# remote-display.net
KiCad netlist of a schematic drawn in EAGLE
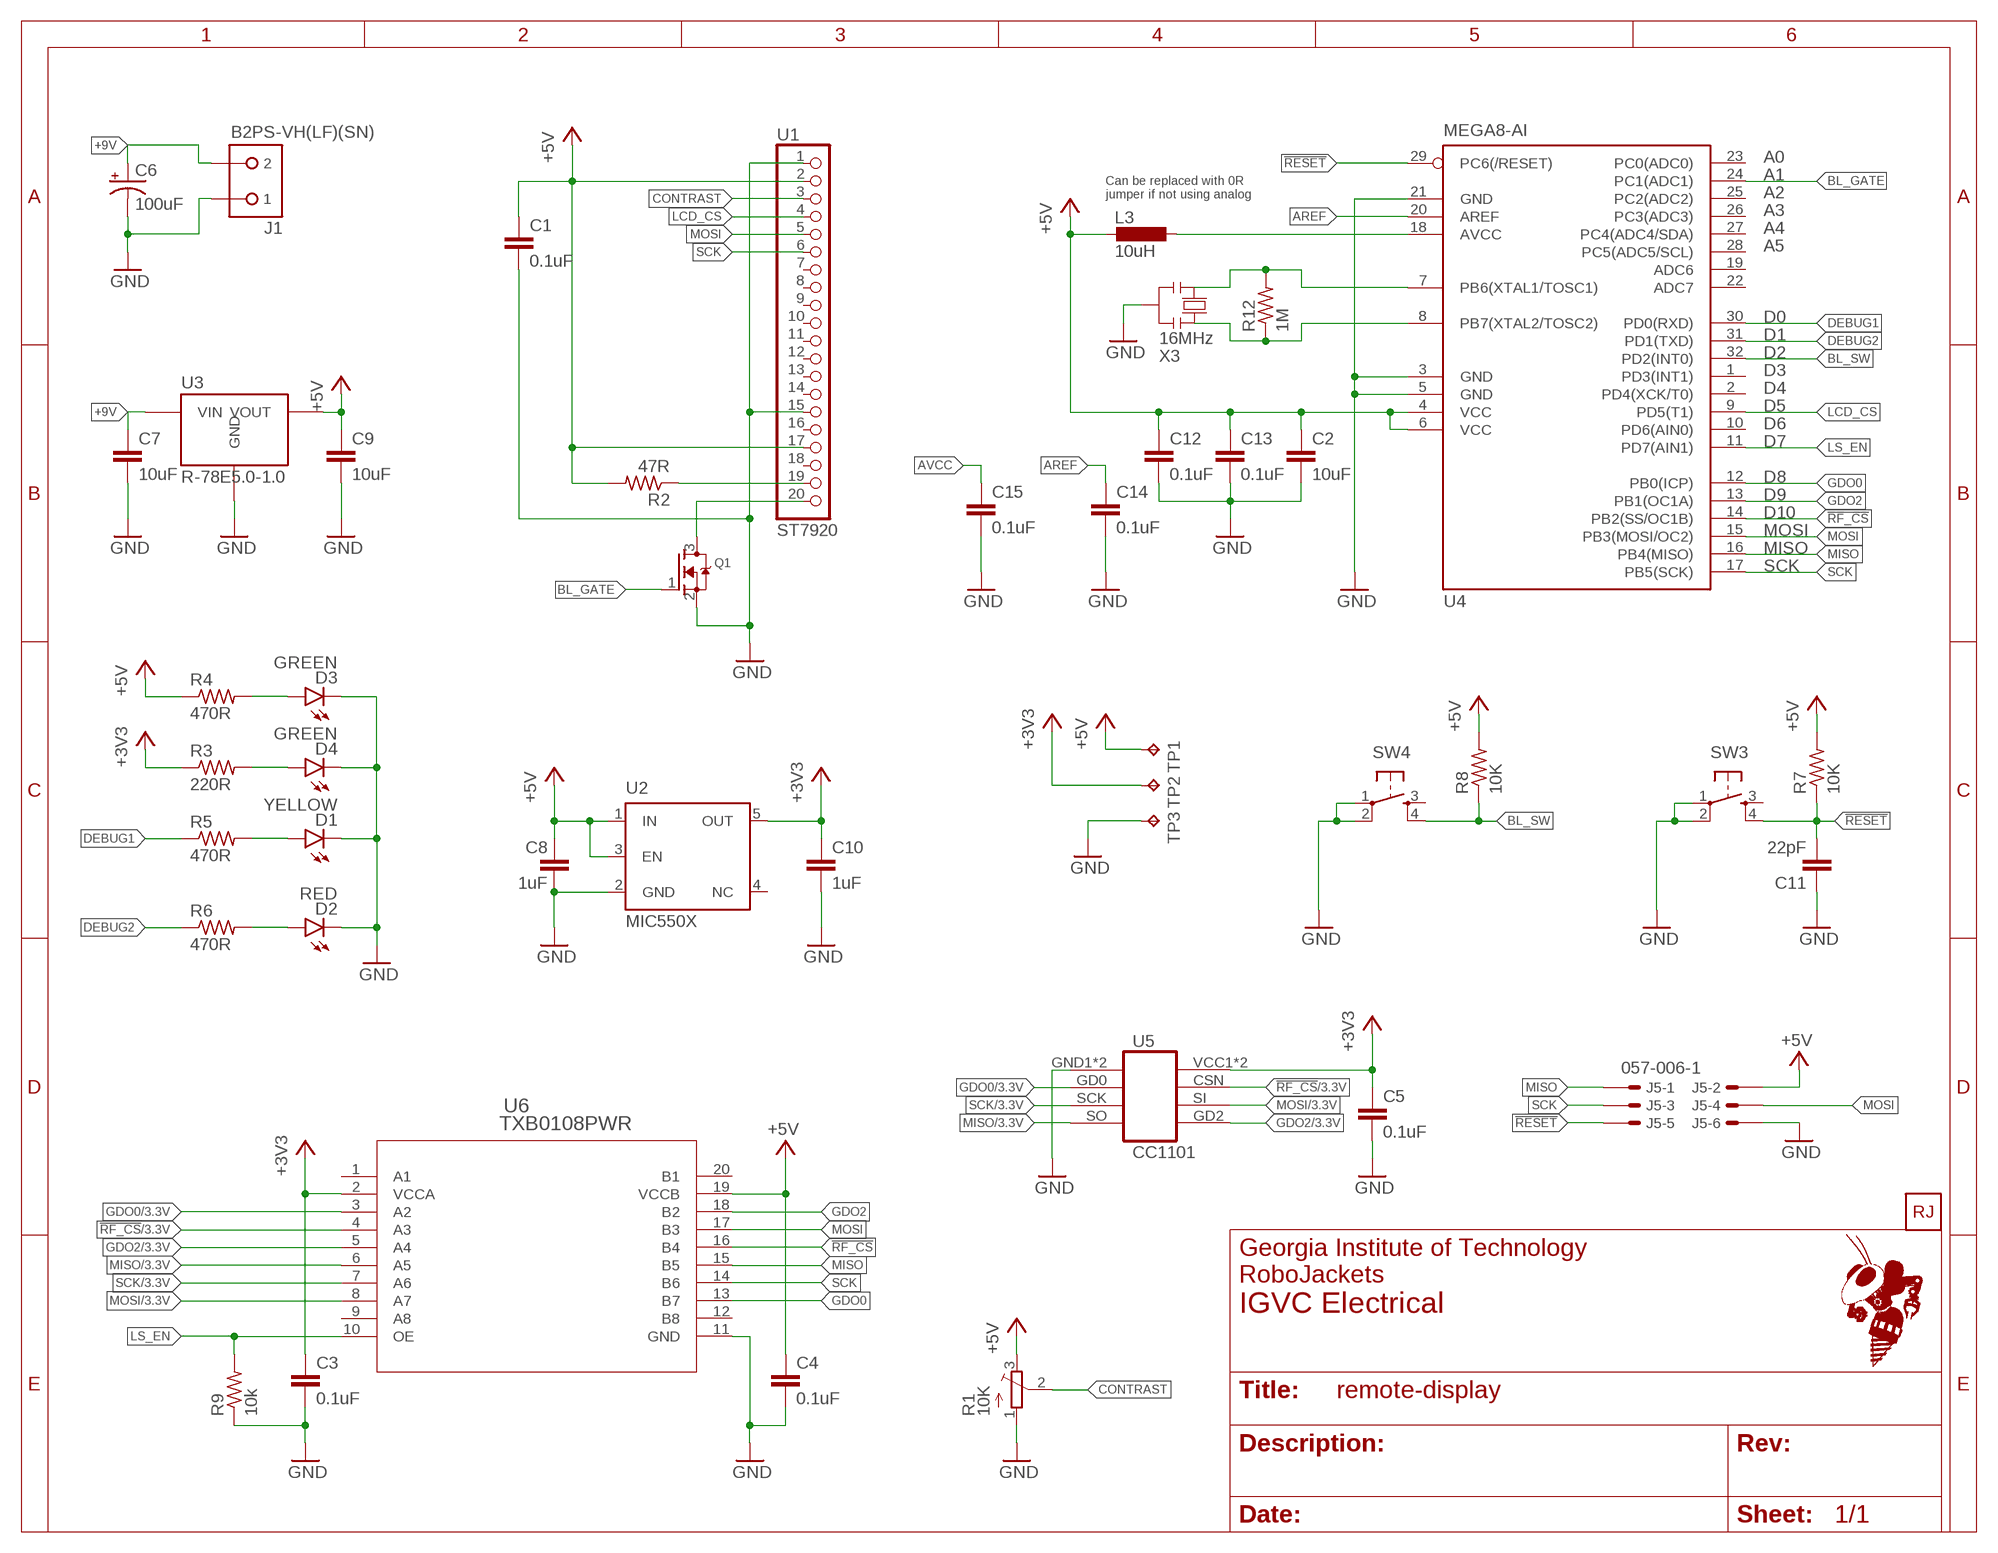
[diagram p0: schematic, sheet 1]

(export (version "E")
  (design (tool "Eeschema 10.0.6"))
  (components
    (comp (ref "C1")
      (value "0.1uF")
      (footprint "eagle-import:C0603")
      (libsource (lib "eagle-import") (part "resistor_348_C-EUC0603"))
    )
    (comp (ref "C2")
      (value "10uF")
      (footprint "eagle-import:C0805")
      (libsource (lib "eagle-import") (part "resistor_348_C-EUC0805"))
    )
    (comp (ref "C3")
      (value "0.1uF")
      (footprint "eagle-import:C0603")
      (libsource (lib "eagle-import") (part "C-EUC0603"))
    )
    (comp (ref "C4")
      (value "0.1uF")
      (footprint "eagle-import:C0603")
      (libsource (lib "eagle-import") (part "C-EUC0603"))
    )
    (comp (ref "C5")
      (value "0.1uF")
      (footprint "eagle-import:C0603")
      (libsource (lib "eagle-import") (part "resistor_348_C-EUC0603"))
    )
    (comp (ref "C6")
      (value "100uF")
      (footprint "eagle-import:E5-10,5")
      (libsource (lib "eagle-import") (part "CPOL-USE5-10.5"))
    )
    (comp (ref "C7")
      (value "10uF")
      (footprint "eagle-import:C0603")
      (libsource (lib "eagle-import") (part "C-EUC0603"))
    )
    (comp (ref "C8")
      (value "1uF")
      (footprint "eagle-import:C0603")
      (libsource (lib "eagle-import") (part "C-EUC0603"))
    )
    (comp (ref "C9")
      (value "10uF")
      (footprint "eagle-import:C0603")
      (libsource (lib "eagle-import") (part "C-EUC0603"))
    )
    (comp (ref "C10")
      (value "1uF")
      (footprint "eagle-import:C0603")
      (libsource (lib "eagle-import") (part "C-EUC0603"))
    )
    (comp (ref "C11")
      (value "22pF")
      (footprint "eagle-import:C0603")
      (libsource (lib "eagle-import") (part "resistor_348_C-EUC0603"))
    )
    (comp (ref "C12")
      (value "0.1uF")
      (footprint "eagle-import:C0603")
      (libsource (lib "eagle-import") (part "resistor_348_C-EUC0603"))
    )
    (comp (ref "C13")
      (value "0.1uF")
      (footprint "eagle-import:C0603")
      (libsource (lib "eagle-import") (part "resistor_348_C-EUC0603"))
    )
    (comp (ref "C14")
      (value "0.1uF")
      (footprint "eagle-import:C0603")
      (libsource (lib "eagle-import") (part "resistor_348_C-EUC0603"))
    )
    (comp (ref "C15")
      (value "0.1uF")
      (footprint "eagle-import:C0603")
      (libsource (lib "eagle-import") (part "resistor_348_C-EUC0603"))
    )
    (comp (ref "D1")
      (value "YELLOW")
      (footprint "eagle-import:LED3MM")
      (libsource (lib "eagle-import") (part "LED3MM"))
    )
    (comp (ref "D2")
      (value "RED")
      (footprint "eagle-import:LED3MM")
      (libsource (lib "eagle-import") (part "LED3MM"))
    )
    (comp (ref "D3")
      (value "GREEN")
      (footprint "eagle-import:LED3MM")
      (libsource (lib "eagle-import") (part "LED3MM"))
    )
    (comp (ref "D4")
      (value "GREEN")
      (footprint "eagle-import:LED3MM")
      (libsource (lib "eagle-import") (part "LED3MM"))
    )
    (comp (ref "J1")
      (value "B2PS-VH(LF)(SN)")
      (footprint "eagle-import:B2PS-CENTERED")
      (libsource (lib "eagle-import") (part "B2P?-VH(LF)(SN)S"))
    )
    (comp (ref "J5")
      (value "057-006-1")
      (footprint "eagle-import:057-006-1")
      (fields (field (name "DIGIKEY") "3M15451-ND"))
      (libsource (lib "eagle-import") (part "057-006-1"))
    )
    (comp (ref "L3")
      (value "10uH")
      (footprint "eagle-import:0805")
      (libsource (lib "eagle-import") (part "L-0805"))
    )
    (comp (ref "Q1")
      (value "MOSFET-NREFLOW")
      (footprint "eagle-import:SOT23")
      (libsource (lib "eagle-import") (part "MOSFET-NREFLOW"))
    )
    (comp (ref "R1")
      (value "10K")
      (footprint "eagle-import:TRIM-3386")
      (libsource (lib "eagle-import") (part "TRIMPOT3386"))
    )
    (comp (ref "R2")
      (value "47R")
      (footprint "eagle-import:R0805")
      (libsource (lib "eagle-import") (part "resistor_348_R-US_R0805"))
    )
    (comp (ref "R3")
      (value "220R")
      (footprint "eagle-import:R0603")
      (libsource (lib "eagle-import") (part "resistor_348_R-US_R0603"))
    )
    (comp (ref "R4")
      (value "470R")
      (footprint "eagle-import:R0603")
      (libsource (lib "eagle-import") (part "resistor_348_R-US_R0603"))
    )
    (comp (ref "R5")
      (value "470R")
      (footprint "eagle-import:R0603")
      (libsource (lib "eagle-import") (part "resistor_348_R-US_R0603"))
    )
    (comp (ref "R6")
      (value "470R")
      (footprint "eagle-import:R0603")
      (libsource (lib "eagle-import") (part "resistor_348_R-US_R0603"))
    )
    (comp (ref "R7")
      (value "10K")
      (footprint "eagle-import:R0603")
      (libsource (lib "eagle-import") (part "resistor_348_R-US_R0603"))
    )
    (comp (ref "R8")
      (value "10K")
      (footprint "eagle-import:R0603")
      (libsource (lib "eagle-import") (part "resistor_348_R-US_R0603"))
    )
    (comp (ref "R9")
      (value "10k")
      (footprint "eagle-import:R0603")
      (libsource (lib "eagle-import") (part "R-US_R0603"))
    )
    (comp (ref "R12")
      (value "1M")
      (footprint "eagle-import:R0603")
      (libsource (lib "eagle-import") (part "resistor_348_R-US_R0603"))
    )
    (comp (ref "SW3")
      (value "TL1105_A-H")
      (footprint "eagle-import:TL1105_A-H")
      (libsource (lib "eagle-import") (part "TL1105_A-H"))
    )
    (comp (ref "SW4")
      (value "TL1105_A-H")
      (footprint "eagle-import:TL1105_A-H")
      (libsource (lib "eagle-import") (part "TL1105_A-H"))
    )
    (comp (ref "TP1")
      (value "TPPAD1-17")
      (footprint "eagle-import:P1-17")
      (libsource (lib "eagle-import") (part "TPPAD1-17"))
    )
    (comp (ref "TP2")
      (value "TPPAD1-17")
      (footprint "eagle-import:P1-17")
      (libsource (lib "eagle-import") (part "TPPAD1-17"))
    )
    (comp (ref "TP3")
      (value "TPPAD1-17")
      (footprint "eagle-import:P1-17")
      (libsource (lib "eagle-import") (part "TPPAD1-17"))
    )
    (comp (ref "U$2")
      (value "ROBOBUZZ1.0X")
      (footprint "eagle-import:ROBOBUZZ_1.0X")
      (libsource (lib "eagle-import") (part "ROBOBUZZ1.0X"))
    )
    (comp (ref "U1")
      (value "ST7920")
      (footprint "eagle-import:ST7920-LCD")
      (libsource (lib "eagle-import") (part "ST7920"))
    )
    (comp (ref "U2")
      (value "MIC550X")
      (footprint "eagle-import:SOT23-DBV")
      (libsource (lib "eagle-import") (part "MIC550X"))
    )
    (comp (ref "U3")
      (value "R-78E5.0-1.0")
      (footprint "eagle-import:R-78E")
      (libsource (lib "eagle-import") (part "R-78E5.0-1.0"))
    )
    (comp (ref "U4")
      (value "MEGA8-AI")
      (footprint "eagle-import:TQFP32-08")
      (fields (field (name "MPN") "ATMEGA8-16AU"))
      (libsource (lib "eagle-import") (part "MEGA8-AI"))
    )
    (comp (ref "U5")
      (value "CC1101")
      (footprint "eagle-import:TI-CC1101")
      (libsource (lib "eagle-import") (part "NRF24L01+PA+LNATI-CC1101"))
    )
    (comp (ref "U6")
      (value "TXB0108PWR")
      (footprint "eagle-import:PW20")
      (libsource (lib "eagle-import") (part "TXB0108PWR"))
    )
    (comp (ref "X3")
      (value "16MHz")
      (footprint "eagle-import:RESONATOR")
      (fields (field (name "PART_NUMBER") "CSTCE16M0V53-R0"))
      (libsource (lib "eagle-import") (part "OSC_CSTCE16M0V53-R0"))
    )
  )
  (nets
    (net (code "1") (name "+3V3") (class "Default")
      (node (ref "C10") (pin "1") (pinfunction "1_1") (pintype "passive"))
      (node (ref "C3") (pin "1") (pinfunction "1_1") (pintype "passive"))
      (node (ref "C5") (pin "1") (pinfunction "1_1") (pintype "passive"))
      (node (ref "R3") (pin "1") (pinfunction "1_1") (pintype "passive"))
      (node (ref "TP2") (pin "TP") (pinfunction "TP_TP") (pintype "input"))
      (node (ref "U2") (pin "5") (pinfunction "OUT_5") (pintype "passive"))
      (node (ref "U5") (pin "VCC1") (pinfunction "VCC_VCC1") (pintype "power_in"))
      (node (ref "U5") (pin "VCC2") (pinfunction "VCC_VCC2") (pintype "power_in"))
      (node (ref "U6") (pin "2") (pinfunction "VCCA_2") (pintype "power_in"))
    )
    (net (code "2") (name "+5V") (class "Default")
      (node (ref "C1") (pin "1") (pinfunction "1_1") (pintype "passive"))
      (node (ref "C12") (pin "1") (pinfunction "1_1") (pintype "passive"))
      (node (ref "C13") (pin "1") (pinfunction "1_1") (pintype "passive"))
      (node (ref "C2") (pin "1") (pinfunction "1_1") (pintype "passive"))
      (node (ref "C4") (pin "1") (pinfunction "1_1") (pintype "passive"))
      (node (ref "C8") (pin "1") (pinfunction "1_1") (pintype "passive"))
      (node (ref "C9") (pin "1") (pinfunction "1_1") (pintype "passive"))
      (node (ref "J5") (pin "2") (pinfunction "S_2") (pintype "passive"))
      (node (ref "L3") (pin "2") (pinfunction "2_2") (pintype "passive"))
      (node (ref "R1") (pin "3") (pinfunction "E_3") (pintype "passive"))
      (node (ref "R2") (pin "2") (pinfunction "2_2") (pintype "passive"))
      (node (ref "R4") (pin "1") (pinfunction "1_1") (pintype "passive"))
      (node (ref "R7") (pin "2") (pinfunction "2_2") (pintype "passive"))
      (node (ref "R8") (pin "2") (pinfunction "2_2") (pintype "passive"))
      (node (ref "TP1") (pin "TP") (pinfunction "TP_TP") (pintype "input"))
      (node (ref "U1") (pin "17") (pinfunction "17_17") (pintype "passive"))
      (node (ref "U1") (pin "2") (pinfunction "2_2") (pintype "passive"))
      (node (ref "U2") (pin "1") (pinfunction "IN_1") (pintype "input"))
      (node (ref "U2") (pin "3") (pinfunction "EN_3") (pintype "input"))
      (node (ref "U3") (pin "3") (pinfunction "VOUT_3") (pintype "bidirectional"))
      (node (ref "U4") (pin "4") (pinfunction "VCC_4") (pintype "power_in"))
      (node (ref "U4") (pin "6") (pinfunction "VCC_6") (pintype "power_in"))
      (node (ref "U6") (pin "19") (pinfunction "VCCB_19") (pintype "power_in"))
    )
    (net (code "3") (name "+9V") (class "Default")
      (node (ref "C6") (pin "+") (pinfunction "+_+") (pintype "passive"))
      (node (ref "C7") (pin "1") (pinfunction "1_1") (pintype "passive"))
      (node (ref "J1") (pin "2") (pinfunction "2_2") (pintype "bidirectional"))
      (node (ref "U3") (pin "1") (pinfunction "VIN_1") (pintype "bidirectional"))
    )
    (net (code "4") (name "/~{RESET}") (class "Default")
      (node (ref "C11") (pin "2") (pinfunction "2_2") (pintype "passive"))
      (node (ref "J5") (pin "5") (pinfunction "S_5") (pintype "passive"))
      (node (ref "R7") (pin "1") (pinfunction "1_1") (pintype "passive"))
      (node (ref "SW3") (pin "4") (pinfunction "4_4") (pintype "passive"))
      (node (ref "U4") (pin "29") (pinfunction "PC6(/RESET)_29") (pintype "bidirectional"))
    )
    (net (code "5") (name "/~{RF_CS}") (class "Default")
      (node (ref "U4") (pin "14") (pinfunction "PB2(SS/OC1B)_14") (pintype "bidirectional"))
      (node (ref "U6") (pin "16") (pinfunction "B4_16") (pintype "bidirectional"))
    )
    (net (code "6") (name "/~{RF_CS}{slash}3.3V") (class "Default")
      (node (ref "U5") (pin "CSN") (pinfunction "CSN_CSN") (pintype "passive"))
      (node (ref "U6") (pin "4") (pinfunction "A3_4") (pintype "bidirectional"))
    )
    (net (code "7") (name "AREF") (class "Default")
      (node (ref "C14") (pin "1") (pinfunction "1_1") (pintype "passive"))
      (node (ref "U4") (pin "20") (pinfunction "AREF_20") (pintype "passive"))
    )
    (net (code "8") (name "AVCC") (class "Default")
      (node (ref "C15") (pin "1") (pinfunction "1_1") (pintype "passive"))
      (node (ref "L3") (pin "1") (pinfunction "1_1") (pintype "passive"))
      (node (ref "U4") (pin "18") (pinfunction "AVCC_18") (pintype "power_in"))
    )
    (net (code "9") (name "BL_GATE") (class "Default")
      (node (ref "Q1") (pin "1") (pinfunction "G_1") (pintype "bidirectional"))
      (node (ref "U4") (pin "24") (pinfunction "PC1(ADC1)_24") (pintype "bidirectional"))
    )
    (net (code "10") (name "BL_SW") (class "Default")
      (node (ref "R8") (pin "1") (pinfunction "1_1") (pintype "passive"))
      (node (ref "SW4") (pin "4") (pinfunction "4_4") (pintype "passive"))
      (node (ref "U4") (pin "32") (pinfunction "PD2(INT0)_32") (pintype "bidirectional"))
    )
    (net (code "11") (name "CONTRAST") (class "Default")
      (node (ref "R1") (pin "2") (pinfunction "S_2") (pintype "passive"))
      (node (ref "U1") (pin "3") (pinfunction "3_3") (pintype "passive"))
    )
    (net (code "12") (name "DEBUG1") (class "Default")
      (node (ref "R5") (pin "1") (pinfunction "1_1") (pintype "passive"))
      (node (ref "U4") (pin "30") (pinfunction "PD0(RXD)_30") (pintype "bidirectional"))
    )
    (net (code "13") (name "DEBUG2") (class "Default")
      (node (ref "R6") (pin "1") (pinfunction "1_1") (pintype "passive"))
      (node (ref "U4") (pin "31") (pinfunction "PD1(TXD)_31") (pintype "bidirectional"))
    )
    (net (code "14") (name "GDO0") (class "Default")
      (node (ref "U4") (pin "12") (pinfunction "PB0(ICP)_12") (pintype "bidirectional"))
      (node (ref "U6") (pin "13") (pinfunction "B7_13") (pintype "bidirectional"))
    )
    (net (code "15") (name "GDO0{slash}3.3V") (class "Default")
      (node (ref "U5") (pin "GD0") (pinfunction "CE_GD0") (pintype "passive"))
      (node (ref "U6") (pin "3") (pinfunction "A2_3") (pintype "bidirectional"))
    )
    (net (code "16") (name "GDO2") (class "Default")
      (node (ref "U4") (pin "13") (pinfunction "PB1(OC1A)_13") (pintype "bidirectional"))
      (node (ref "U6") (pin "18") (pinfunction "B2_18") (pintype "bidirectional"))
    )
    (net (code "17") (name "GDO2{slash}3.3V") (class "Default")
      (node (ref "U5") (pin "GD2") (pinfunction "IRQ_GD2") (pintype "passive"))
      (node (ref "U6") (pin "5") (pinfunction "A4_5") (pintype "bidirectional"))
    )
    (net (code "18") (name "GND") (class "Default")
      (node (ref "C1") (pin "2") (pinfunction "2_2") (pintype "passive"))
      (node (ref "C10") (pin "2") (pinfunction "2_2") (pintype "passive"))
      (node (ref "C11") (pin "1") (pinfunction "1_1") (pintype "passive"))
      (node (ref "C12") (pin "2") (pinfunction "2_2") (pintype "passive"))
      (node (ref "C13") (pin "2") (pinfunction "2_2") (pintype "passive"))
      (node (ref "C14") (pin "2") (pinfunction "2_2") (pintype "passive"))
      (node (ref "C15") (pin "2") (pinfunction "2_2") (pintype "passive"))
      (node (ref "C2") (pin "2") (pinfunction "2_2") (pintype "passive"))
      (node (ref "C3") (pin "2") (pinfunction "2_2") (pintype "passive"))
      (node (ref "C4") (pin "2") (pinfunction "2_2") (pintype "passive"))
      (node (ref "C5") (pin "2") (pinfunction "2_2") (pintype "passive"))
      (node (ref "C6") (pin "-") (pinfunction "-_-") (pintype "passive"))
      (node (ref "C7") (pin "2") (pinfunction "2_2") (pintype "passive"))
      (node (ref "C8") (pin "2") (pinfunction "2_2") (pintype "passive"))
      (node (ref "C9") (pin "2") (pinfunction "2_2") (pintype "passive"))
      (node (ref "D1") (pin "K") (pinfunction "C_K") (pintype "passive"))
      (node (ref "D2") (pin "K") (pinfunction "C_K") (pintype "passive"))
      (node (ref "D3") (pin "K") (pinfunction "C_K") (pintype "passive"))
      (node (ref "D4") (pin "K") (pinfunction "C_K") (pintype "passive"))
      (node (ref "J1") (pin "1") (pinfunction "1_1") (pintype "bidirectional"))
      (node (ref "J5") (pin "6") (pinfunction "S_6") (pintype "passive"))
      (node (ref "Q1") (pin "2") (pinfunction "S_2") (pintype "bidirectional"))
      (node (ref "R1") (pin "1") (pinfunction "A_1") (pintype "passive"))
      (node (ref "R9") (pin "1") (pinfunction "1_1") (pintype "passive"))
      (node (ref "SW3") (pin "1") (pinfunction "1_1") (pintype "passive"))
      (node (ref "SW3") (pin "2") (pinfunction "2_2") (pintype "passive"))
      (node (ref "SW4") (pin "1") (pinfunction "1_1") (pintype "passive"))
      (node (ref "SW4") (pin "2") (pinfunction "2_2") (pintype "passive"))
      (node (ref "TP3") (pin "TP") (pinfunction "TP_TP") (pintype "input"))
      (node (ref "U1") (pin "1") (pinfunction "1_1") (pintype "passive"))
      (node (ref "U1") (pin "15") (pinfunction "15_15") (pintype "passive"))
      (node (ref "U2") (pin "2") (pinfunction "GND_2") (pintype "output"))
      (node (ref "U3") (pin "2") (pinfunction "GND_2") (pintype "bidirectional"))
      (node (ref "U4") (pin "21") (pinfunction "GND_21") (pintype "power_in"))
      (node (ref "U4") (pin "3") (pinfunction "GND_3") (pintype "power_in"))
      (node (ref "U4") (pin "5") (pinfunction "GND_5") (pintype "power_in"))
      (node (ref "U5") (pin "GND1") (pinfunction "GND_GND1") (pintype "power_in"))
      (node (ref "U5") (pin "GND2") (pinfunction "GND_GND2") (pintype "power_in"))
      (node (ref "U6") (pin "11") (pinfunction "GND_11") (pintype "power_in"))
      (node (ref "X3") (pin "2") (pinfunction "2_2") (pintype "passive"))
    )
    (net (code "19") (name "LCD_CS") (class "Default")
      (node (ref "U1") (pin "4") (pinfunction "4_4") (pintype "passive"))
      (node (ref "U4") (pin "9") (pinfunction "PD5(T1)_9") (pintype "bidirectional"))
    )
    (net (code "20") (name "LS_EN") (class "Default")
      (node (ref "R9") (pin "2") (pinfunction "2_2") (pintype "passive"))
      (node (ref "U4") (pin "11") (pinfunction "PD7(AIN1)_11") (pintype "bidirectional"))
      (node (ref "U6") (pin "10") (pinfunction "OE_10") (pintype "output"))
    )
    (net (code "21") (name "MISO") (class "Default")
      (node (ref "J5") (pin "1") (pinfunction "S_1") (pintype "passive"))
      (node (ref "U4") (pin "16") (pinfunction "PB4(MISO)_16") (pintype "bidirectional"))
      (node (ref "U6") (pin "15") (pinfunction "B5_15") (pintype "bidirectional"))
    )
    (net (code "22") (name "MISO{slash}3.3V") (class "Default")
      (node (ref "U5") (pin "SO") (pinfunction "MISO_SO") (pintype "passive"))
      (node (ref "U6") (pin "6") (pinfunction "A5_6") (pintype "bidirectional"))
    )
    (net (code "23") (name "MOSI") (class "Default")
      (node (ref "J5") (pin "4") (pinfunction "S_4") (pintype "passive"))
      (node (ref "U1") (pin "5") (pinfunction "5_5") (pintype "passive"))
      (node (ref "U4") (pin "15") (pinfunction "PB3(MOSI/OC2)_15") (pintype "bidirectional"))
      (node (ref "U6") (pin "17") (pinfunction "B3_17") (pintype "bidirectional"))
    )
    (net (code "24") (name "MOSI{slash}3.3V") (class "Default")
      (node (ref "U5") (pin "SI") (pinfunction "MOSI_SI") (pintype "passive"))
      (node (ref "U6") (pin "8") (pinfunction "A7_8") (pintype "bidirectional"))
    )
    (net (code "25") (name "Net-(D1-PadA)") (class "Default")
      (node (ref "D1") (pin "A") (pinfunction "A_A") (pintype "passive"))
      (node (ref "R5") (pin "2") (pinfunction "2_2") (pintype "passive"))
    )
    (net (code "26") (name "Net-(D2-PadA)") (class "Default")
      (node (ref "D2") (pin "A") (pinfunction "A_A") (pintype "passive"))
      (node (ref "R6") (pin "2") (pinfunction "2_2") (pintype "passive"))
    )
    (net (code "27") (name "Net-(D3-PadA)") (class "Default")
      (node (ref "D3") (pin "A") (pinfunction "A_A") (pintype "passive"))
      (node (ref "R4") (pin "2") (pinfunction "2_2") (pintype "passive"))
    )
    (net (code "28") (name "Net-(D4-PadA)") (class "Default")
      (node (ref "D4") (pin "A") (pinfunction "A_A") (pintype "passive"))
      (node (ref "R3") (pin "2") (pinfunction "2_2") (pintype "passive"))
    )
    (net (code "29") (name "Net-(Q1-D)") (class "Default")
      (node (ref "Q1") (pin "3") (pinfunction "D_3") (pintype "bidirectional"))
      (node (ref "U1") (pin "20") (pinfunction "20_20") (pintype "passive"))
    )
    (net (code "30") (name "Net-(R2-Pad1)") (class "Default")
      (node (ref "R2") (pin "1") (pinfunction "1_1") (pintype "passive"))
      (node (ref "U1") (pin "19") (pinfunction "19_19") (pintype "passive"))
    )
    (net (code "31") (name "Net-(U4-PB6(XTAL1{slash}TOSC1))") (class "Default")
      (node (ref "R12") (pin "2") (pinfunction "2_2") (pintype "passive"))
      (node (ref "U4") (pin "7") (pinfunction "PB6(XTAL1/TOSC1)_7") (pintype "bidirectional"))
      (node (ref "X3") (pin "1") (pinfunction "1_1") (pintype "passive"))
    )
    (net (code "32") (name "Net-(U4-PB7(XTAL2{slash}TOSC2))") (class "Default")
      (node (ref "R12") (pin "1") (pinfunction "1_1") (pintype "passive"))
      (node (ref "U4") (pin "8") (pinfunction "PB7(XTAL2/TOSC2)_8") (pintype "bidirectional"))
      (node (ref "X3") (pin "3") (pinfunction "3_3") (pintype "passive"))
    )
    (net (code "33") (name "SCK") (class "Default")
      (node (ref "J5") (pin "3") (pinfunction "S_3") (pintype "passive"))
      (node (ref "U1") (pin "6") (pinfunction "6_6") (pintype "passive"))
      (node (ref "U4") (pin "17") (pinfunction "PB5(SCK)_17") (pintype "bidirectional"))
      (node (ref "U6") (pin "14") (pinfunction "B6_14") (pintype "bidirectional"))
    )
    (net (code "34") (name "SCK{slash}3.3V") (class "Default")
      (node (ref "U5") (pin "SCK") (pinfunction "SCK_SCK") (pintype "passive"))
      (node (ref "U6") (pin "7") (pinfunction "A6_7") (pintype "bidirectional"))
    )
    (net (code "35") (name "unconnected-(SW3-Pad3)") (class "Default")
      (node (ref "SW3") (pin "3") (pinfunction "3_3") (pintype "passive"))
    )
    (net (code "36") (name "unconnected-(SW4-Pad3)") (class "Default")
      (node (ref "SW4") (pin "3") (pinfunction "3_3") (pintype "passive"))
    )
    (net (code "37") (name "unconnected-(U1-Pad7)") (class "Default")
      (node (ref "U1") (pin "7") (pinfunction "7_7") (pintype "passive"))
    )
    (net (code "38") (name "unconnected-(U1-Pad8)") (class "Default")
      (node (ref "U1") (pin "8") (pinfunction "8_8") (pintype "passive"))
    )
    (net (code "39") (name "unconnected-(U1-Pad9)") (class "Default")
      (node (ref "U1") (pin "9") (pinfunction "9_9") (pintype "passive"))
    )
    (net (code "40") (name "unconnected-(U1-Pad10)") (class "Default")
      (node (ref "U1") (pin "10") (pinfunction "10_10") (pintype "passive"))
    )
    (net (code "41") (name "unconnected-(U1-Pad11)") (class "Default")
      (node (ref "U1") (pin "11") (pinfunction "11_11") (pintype "passive"))
    )
    (net (code "42") (name "unconnected-(U1-Pad12)") (class "Default")
      (node (ref "U1") (pin "12") (pinfunction "12_12") (pintype "passive"))
    )
    (net (code "43") (name "unconnected-(U1-Pad13)") (class "Default")
      (node (ref "U1") (pin "13") (pinfunction "13_13") (pintype "passive"))
    )
    (net (code "44") (name "unconnected-(U1-Pad14)") (class "Default")
      (node (ref "U1") (pin "14") (pinfunction "14_14") (pintype "passive"))
    )
    (net (code "45") (name "unconnected-(U1-Pad16)") (class "Default")
      (node (ref "U1") (pin "16") (pinfunction "16_16") (pintype "passive"))
    )
    (net (code "46") (name "unconnected-(U1-Pad18)") (class "Default")
      (node (ref "U1") (pin "18") (pinfunction "18_18") (pintype "passive"))
    )
    (net (code "47") (name "unconnected-(U2-NC-Pad4)") (class "Default")
      (node (ref "U2") (pin "4") (pinfunction "NC_4") (pintype "tri_state"))
    )
    (net (code "48") (name "unconnected-(U4-ADC6-Pad19)") (class "Default")
      (node (ref "U4") (pin "19") (pinfunction "ADC6_19") (pintype "bidirectional"))
    )
    (net (code "49") (name "unconnected-(U4-ADC7-Pad22)") (class "Default")
      (node (ref "U4") (pin "22") (pinfunction "ADC7_22") (pintype "bidirectional"))
    )
    (net (code "50") (name "unconnected-(U4-PC0(ADC0)-Pad23)") (class "Default")
      (node (ref "U4") (pin "23") (pinfunction "PC0(ADC0)_23") (pintype "bidirectional"))
    )
    (net (code "51") (name "unconnected-(U4-PC2(ADC2)-Pad25)") (class "Default")
      (node (ref "U4") (pin "25") (pinfunction "PC2(ADC2)_25") (pintype "bidirectional"))
    )
    (net (code "52") (name "unconnected-(U4-PC3(ADC3)-Pad26)") (class "Default")
      (node (ref "U4") (pin "26") (pinfunction "PC3(ADC3)_26") (pintype "bidirectional"))
    )
    (net (code "53") (name "unconnected-(U4-PC4(ADC4{slash}SDA)-Pad27)") (class "Default")
      (node (ref "U4") (pin "27") (pinfunction "PC4(ADC4/SDA)_27") (pintype "bidirectional"))
    )
    (net (code "54") (name "unconnected-(U4-PC5(ADC5{slash}SCL)-Pad28)") (class "Default")
      (node (ref "U4") (pin "28") (pinfunction "PC5(ADC5/SCL)_28") (pintype "bidirectional"))
    )
    (net (code "55") (name "unconnected-(U4-PD3(INT1)-Pad1)") (class "Default")
      (node (ref "U4") (pin "1") (pinfunction "PD3(INT1)_1") (pintype "bidirectional"))
    )
    (net (code "56") (name "unconnected-(U4-PD4(XCK{slash}T0)-Pad2)") (class "Default")
      (node (ref "U4") (pin "2") (pinfunction "PD4(XCK/T0)_2") (pintype "bidirectional"))
    )
    (net (code "57") (name "unconnected-(U4-PD6(AIN0)-Pad10)") (class "Default")
      (node (ref "U4") (pin "10") (pinfunction "PD6(AIN0)_10") (pintype "bidirectional"))
    )
    (net (code "58") (name "unconnected-(U6-A1-Pad1)") (class "Default")
      (node (ref "U6") (pin "1") (pinfunction "A1_1") (pintype "bidirectional"))
    )
    (net (code "59") (name "unconnected-(U6-A8-Pad9)") (class "Default")
      (node (ref "U6") (pin "9") (pinfunction "A8_9") (pintype "bidirectional"))
    )
    (net (code "60") (name "unconnected-(U6-B1-Pad20)") (class "Default")
      (node (ref "U6") (pin "20") (pinfunction "B1_20") (pintype "bidirectional"))
    )
    (net (code "61") (name "unconnected-(U6-B8-Pad12)") (class "Default")
      (node (ref "U6") (pin "12") (pinfunction "B8_12") (pintype "bidirectional"))
    )
  )
)
